# NTC_connector.net
KiCad netlist of a schematic drawn in Altium Designer
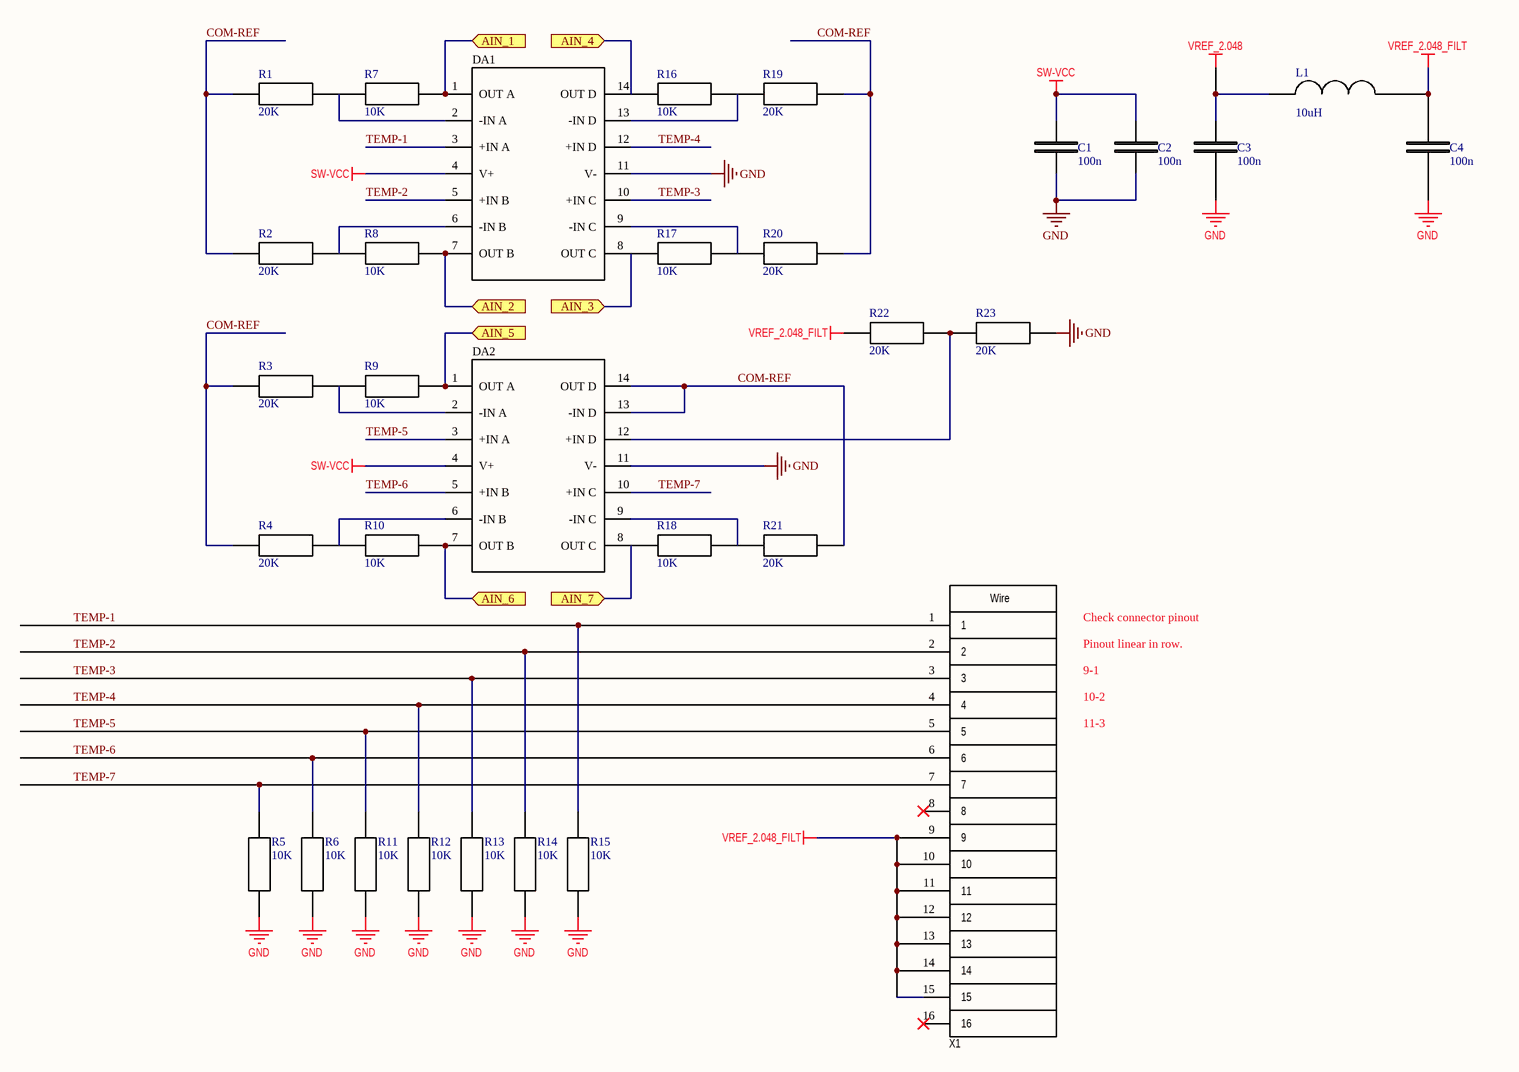
[diagram p0: NTC connector.SchDoc]

(export (version "E")
  (design (tool "Eeschema 10.0.6"))
  (components
    (comp (ref "C1")
      (value "100n")
      (footprint "CAP0402")
      (description "0402 SMD")
      (fields (field (name "PARTNUMBER") "CC0402ZRY5V7BB104") (field (name "MANUFACTURER") "Yageo"))
      (libsource (lib "capasitors") (part "100n SMD 0402"))
    )
    (comp (ref "C2")
      (value "100n")
      (footprint "CAP0402")
      (description "0402 SMD")
      (fields (field (name "PARTNUMBER") "CC0402ZRY5V7BB104") (field (name "MANUFACTURER") "Yageo"))
      (libsource (lib "capasitors") (part "100n SMD 0402"))
    )
    (comp (ref "C3")
      (value "100n")
      (footprint "CAP0402")
      (description "0402 SMD")
      (fields (field (name "PARTNUMBER") "CC0402ZRY5V7BB104") (field (name "MANUFACTURER") "Yageo"))
      (libsource (lib "capasitors") (part "100n SMD 0402"))
    )
    (comp (ref "C4")
      (value "100n")
      (footprint "CAP0402")
      (description "0402 SMD")
      (fields (field (name "PARTNUMBER") "CC0402ZRY5V7BB104") (field (name "MANUFACTURER") "Yageo"))
      (libsource (lib "capasitors") (part "100n SMD 0402"))
    )
    (comp (ref "DA1")
      (value "OPA4376")
      (footprint "TSSOP-14")
      (description "Opamp  2.2-5.5 V, Offset 5μV")
      (fields (field (name "PARTNUMBER") "OPA4376AIPW") (field (name "MANUFACTURER") "Texas Instruments"))
      (libsource (lib "opamp") (part "OPA4376"))
    )
    (comp (ref "DA2")
      (value "OPA4376")
      (footprint "TSSOP-14")
      (description "Opamp  2.2-5.5 V, Offset 5μV")
      (fields (field (name "PARTNUMBER") "OPA4376AIPW") (field (name "MANUFACTURER") "Texas Instruments"))
      (libsource (lib "opamp") (part "OPA4376"))
    )
    (comp (ref "L1")
      (value "10uH")
      (footprint "IND0805")
      (description "0805 SMD")
      (fields (field (name "PARTNUMBER") "LQM21FN100M80L") (field (name "MANUFACTURER") "Murata"))
      (libsource (lib "inductors") (part "IND 10uH SMD 0805"))
    )
    (comp (ref "R1")
      (value "20K")
      (footprint "RES0402")
      (description "1% 0402 SMD 0.063W")
      (fields (field (name "PARTNUMBER") "RC0402FR-0720KL") (field (name "MANUFACTURER") "Yageo"))
      (libsource (lib "resistors") (part "20K 1% SMD 0402"))
    )
    (comp (ref "R2")
      (value "20K")
      (footprint "RES0402")
      (description "1% 0402 SMD 0.063W")
      (fields (field (name "PARTNUMBER") "RC0402FR-0720KL") (field (name "MANUFACTURER") "Yageo"))
      (libsource (lib "resistors") (part "20K 1% SMD 0402"))
    )
    (comp (ref "R3")
      (value "20K")
      (footprint "RES0402")
      (description "1% 0402 SMD 0.063W")
      (fields (field (name "PARTNUMBER") "RC0402FR-0720KL") (field (name "MANUFACTURER") "Yageo"))
      (libsource (lib "resistors") (part "20K 1% SMD 0402"))
    )
    (comp (ref "R4")
      (value "20K")
      (footprint "RES0402")
      (description "1% 0402 SMD 0.063W")
      (fields (field (name "PARTNUMBER") "RC0402FR-0720KL") (field (name "MANUFACTURER") "Yageo"))
      (libsource (lib "resistors") (part "20K 1% SMD 0402"))
    )
    (comp (ref "R5")
      (value "10K")
      (footprint "RES0402")
      (description "1% 0402 SMD 0.063W")
      (fields (field (name "PARTNUMBER") "RC0402FR-0710KL") (field (name "MANUFACTURER") "Yageo"))
      (libsource (lib "resistors") (part "10K 1% SMD 0402"))
    )
    (comp (ref "R6")
      (value "10K")
      (footprint "RES0402")
      (description "1% 0402 SMD 0.063W")
      (fields (field (name "PARTNUMBER") "RC0402FR-0710KL") (field (name "MANUFACTURER") "Yageo"))
      (libsource (lib "resistors") (part "10K 1% SMD 0402"))
    )
    (comp (ref "R7")
      (value "10K")
      (footprint "RES0402")
      (description "1% 0402 SMD 0.063W")
      (fields (field (name "PARTNUMBER") "RC0402FR-0710KL") (field (name "MANUFACTURER") "Yageo"))
      (libsource (lib "resistors") (part "10K 1% SMD 0402"))
    )
    (comp (ref "R8")
      (value "10K")
      (footprint "RES0402")
      (description "1% 0402 SMD 0.063W")
      (fields (field (name "PARTNUMBER") "RC0402FR-0710KL") (field (name "MANUFACTURER") "Yageo"))
      (libsource (lib "resistors") (part "10K 1% SMD 0402"))
    )
    (comp (ref "R9")
      (value "10K")
      (footprint "RES0402")
      (description "1% 0402 SMD 0.063W")
      (fields (field (name "PARTNUMBER") "RC0402FR-0710KL") (field (name "MANUFACTURER") "Yageo"))
      (libsource (lib "resistors") (part "10K 1% SMD 0402"))
    )
    (comp (ref "R10")
      (value "10K")
      (footprint "RES0402")
      (description "1% 0402 SMD 0.063W")
      (fields (field (name "PARTNUMBER") "RC0402FR-0710KL") (field (name "MANUFACTURER") "Yageo"))
      (libsource (lib "resistors") (part "10K 1% SMD 0402"))
    )
    (comp (ref "R11")
      (value "10K")
      (footprint "RES0402")
      (description "1% 0402 SMD 0.063W")
      (fields (field (name "PARTNUMBER") "RC0402FR-0710KL") (field (name "MANUFACTURER") "Yageo"))
      (libsource (lib "resistors") (part "10K 1% SMD 0402"))
    )
    (comp (ref "R12")
      (value "10K")
      (footprint "RES0402")
      (description "1% 0402 SMD 0.063W")
      (fields (field (name "PARTNUMBER") "RC0402FR-0710KL") (field (name "MANUFACTURER") "Yageo"))
      (libsource (lib "resistors") (part "10K 1% SMD 0402"))
    )
    (comp (ref "R13")
      (value "10K")
      (footprint "RES0402")
      (description "1% 0402 SMD 0.063W")
      (fields (field (name "PARTNUMBER") "RC0402FR-0710KL") (field (name "MANUFACTURER") "Yageo"))
      (libsource (lib "resistors") (part "10K 1% SMD 0402"))
    )
    (comp (ref "R14")
      (value "10K")
      (footprint "RES0402")
      (description "1% 0402 SMD 0.063W")
      (fields (field (name "PARTNUMBER") "RC0402FR-0710KL") (field (name "MANUFACTURER") "Yageo"))
      (libsource (lib "resistors") (part "10K 1% SMD 0402"))
    )
    (comp (ref "R15")
      (value "10K")
      (footprint "RES0402")
      (description "1% 0402 SMD 0.063W")
      (fields (field (name "PARTNUMBER") "RC0402FR-0710KL") (field (name "MANUFACTURER") "Yageo"))
      (libsource (lib "resistors") (part "10K 1% SMD 0402"))
    )
    (comp (ref "R16")
      (value "10K")
      (footprint "RES0402")
      (description "1% 0402 SMD 0.063W")
      (fields (field (name "PARTNUMBER") "RC0402FR-0710KL") (field (name "MANUFACTURER") "Yageo"))
      (libsource (lib "resistors") (part "10K 1% SMD 0402"))
    )
    (comp (ref "R17")
      (value "10K")
      (footprint "RES0402")
      (description "1% 0402 SMD 0.063W")
      (fields (field (name "PARTNUMBER") "RC0402FR-0710KL") (field (name "MANUFACTURER") "Yageo"))
      (libsource (lib "resistors") (part "10K 1% SMD 0402"))
    )
    (comp (ref "R18")
      (value "10K")
      (footprint "RES0402")
      (description "1% 0402 SMD 0.063W")
      (fields (field (name "PARTNUMBER") "RC0402FR-0710KL") (field (name "MANUFACTURER") "Yageo"))
      (libsource (lib "resistors") (part "10K 1% SMD 0402"))
    )
    (comp (ref "R19")
      (value "20K")
      (footprint "RES0402")
      (description "1% 0402 SMD 0.063W")
      (fields (field (name "PARTNUMBER") "RC0402FR-0720KL") (field (name "MANUFACTURER") "Yageo"))
      (libsource (lib "resistors") (part "20K 1% SMD 0402"))
    )
    (comp (ref "R20")
      (value "20K")
      (footprint "RES0402")
      (description "1% 0402 SMD 0.063W")
      (fields (field (name "PARTNUMBER") "RC0402FR-0720KL") (field (name "MANUFACTURER") "Yageo"))
      (libsource (lib "resistors") (part "20K 1% SMD 0402"))
    )
    (comp (ref "R21")
      (value "20K")
      (footprint "RES0402")
      (description "1% 0402 SMD 0.063W")
      (fields (field (name "PARTNUMBER") "RC0402FR-0720KL") (field (name "MANUFACTURER") "Yageo"))
      (libsource (lib "resistors") (part "20K 1% SMD 0402"))
    )
    (comp (ref "R22")
      (value "20K")
      (footprint "RES0402")
      (description "1% 0402 SMD 0.063W")
      (fields (field (name "PARTNUMBER") "RC0402FR-0720KL") (field (name "MANUFACTURER") "Yageo"))
      (libsource (lib "resistors") (part "20K 1% SMD 0402"))
    )
    (comp (ref "R23")
      (value "20K")
      (footprint "RES0402")
      (description "1% 0402 SMD 0.063W")
      (fields (field (name "PARTNUMBER") "RC0402FR-0720KL") (field (name "MANUFACTURER") "Yageo"))
      (libsource (lib "resistors") (part "20K 1% SMD 0402"))
    )
    (comp (ref "X1")
      (value "Microfit3.0 16 pins R thru hole")
      (footprint "microfit30_16")
      (description "Step 3mm, dual row 16 pins, thru hole")
      (fields (field (name "PARTNUMBER") "43045-1601 molex") (field (name "MANUFACTURER") "Molex"))
      (libsource (lib "connectors") (part "Microfit3.0 16 pins R thru hole"))
    )
  )
  (nets
    (net (code "1") (name "/AIN_1") (class "Default")
      (node (ref "DA1") (pin "1") (pinfunction "OUT_A_1") (pintype "passive"))
      (node (ref "R7") (pin "1") (pinfunction "1_1") (pintype "passive"))
    )
    (net (code "2") (name "/AIN_2") (class "Default")
      (node (ref "DA1") (pin "7") (pinfunction "OUT_B_7") (pintype "passive"))
      (node (ref "R8") (pin "1") (pinfunction "1_1") (pintype "passive"))
    )
    (net (code "3") (name "/AIN_3") (class "Default")
      (node (ref "DA1") (pin "8") (pinfunction "OUT_C_8") (pintype "passive"))
      (node (ref "R17") (pin "2") (pinfunction "2_2") (pintype "passive"))
    )
    (net (code "4") (name "/AIN_4") (class "Default")
      (node (ref "DA1") (pin "14") (pinfunction "OUT_D_14") (pintype "passive"))
      (node (ref "R16") (pin "2") (pinfunction "2_2") (pintype "passive"))
    )
    (net (code "5") (name "/AIN_5") (class "Default")
      (node (ref "DA2") (pin "1") (pinfunction "OUT_A_1") (pintype "passive"))
      (node (ref "R9") (pin "1") (pinfunction "1_1") (pintype "passive"))
    )
    (net (code "6") (name "/AIN_6") (class "Default")
      (node (ref "DA2") (pin "7") (pinfunction "OUT_B_7") (pintype "passive"))
      (node (ref "R10") (pin "1") (pinfunction "1_1") (pintype "passive"))
    )
    (net (code "7") (name "/AIN_7") (class "Default")
      (node (ref "DA2") (pin "8") (pinfunction "OUT_C_8") (pintype "passive"))
      (node (ref "R18") (pin "2") (pinfunction "2_2") (pintype "passive"))
    )
    (net (code "8") (name "/COM-REF") (class "Default")
      (node (ref "DA2") (pin "13") (pinfunction "-IN_D_13") (pintype "passive"))
      (node (ref "DA2") (pin "14") (pinfunction "OUT_D_14") (pintype "passive"))
      (node (ref "R1") (pin "2") (pinfunction "2_2") (pintype "passive"))
      (node (ref "R19") (pin "1") (pinfunction "1_1") (pintype "passive"))
      (node (ref "R2") (pin "2") (pinfunction "2_2") (pintype "passive"))
      (node (ref "R20") (pin "1") (pinfunction "1_1") (pintype "passive"))
      (node (ref "R21") (pin "1") (pinfunction "1_1") (pintype "passive"))
      (node (ref "R3") (pin "2") (pinfunction "2_2") (pintype "passive"))
      (node (ref "R4") (pin "2") (pinfunction "2_2") (pintype "passive"))
    )
    (net (code "9") (name "/TEMP-1") (class "Default")
      (node (ref "DA1") (pin "3") (pinfunction "+IN_A_3") (pintype "passive"))
      (node (ref "R15") (pin "1") (pinfunction "1_1") (pintype "passive"))
      (node (ref "X1") (pin "1") (pinfunction "1_1") (pintype "passive"))
    )
    (net (code "10") (name "/TEMP-2") (class "Default")
      (node (ref "DA1") (pin "5") (pinfunction "+IN_B_5") (pintype "passive"))
      (node (ref "R14") (pin "1") (pinfunction "1_1") (pintype "passive"))
      (node (ref "X1") (pin "2") (pinfunction "2_2") (pintype "passive"))
    )
    (net (code "11") (name "/TEMP-3") (class "Default")
      (node (ref "DA1") (pin "10") (pinfunction "+IN_C_10") (pintype "passive"))
      (node (ref "R13") (pin "1") (pinfunction "1_1") (pintype "passive"))
      (node (ref "X1") (pin "3") (pinfunction "3_3") (pintype "passive"))
    )
    (net (code "12") (name "/TEMP-4") (class "Default")
      (node (ref "DA1") (pin "12") (pinfunction "+IN_D_12") (pintype "passive"))
      (node (ref "R12") (pin "1") (pinfunction "1_1") (pintype "passive"))
      (node (ref "X1") (pin "4") (pinfunction "4_4") (pintype "passive"))
    )
    (net (code "13") (name "/TEMP-5") (class "Default")
      (node (ref "DA2") (pin "3") (pinfunction "+IN_A_3") (pintype "passive"))
      (node (ref "R11") (pin "1") (pinfunction "1_1") (pintype "passive"))
      (node (ref "X1") (pin "5") (pinfunction "5_5") (pintype "passive"))
    )
    (net (code "14") (name "/TEMP-6") (class "Default")
      (node (ref "DA2") (pin "5") (pinfunction "+IN_B_5") (pintype "passive"))
      (node (ref "R6") (pin "1") (pinfunction "1_1") (pintype "passive"))
      (node (ref "X1") (pin "6") (pinfunction "6_6") (pintype "passive"))
    )
    (net (code "15") (name "/TEMP-7") (class "Default")
      (node (ref "DA2") (pin "10") (pinfunction "+IN_C_10") (pintype "passive"))
      (node (ref "R5") (pin "1") (pinfunction "1_1") (pintype "passive"))
      (node (ref "X1") (pin "7") (pinfunction "7_7") (pintype "passive"))
    )
    (net (code "16") (name "GND") (class "Default")
      (node (ref "C1") (pin "2") (pinfunction "2_2") (pintype "passive"))
      (node (ref "C2") (pin "2") (pinfunction "2_2") (pintype "passive"))
      (node (ref "C3") (pin "2") (pinfunction "2_2") (pintype "passive"))
      (node (ref "C4") (pin "2") (pinfunction "2_2") (pintype "passive"))
      (node (ref "DA1") (pin "11") (pinfunction "V-_11") (pintype "passive"))
      (node (ref "DA2") (pin "11") (pinfunction "V-_11") (pintype "passive"))
      (node (ref "R11") (pin "2") (pinfunction "2_2") (pintype "passive"))
      (node (ref "R12") (pin "2") (pinfunction "2_2") (pintype "passive"))
      (node (ref "R13") (pin "2") (pinfunction "2_2") (pintype "passive"))
      (node (ref "R14") (pin "2") (pinfunction "2_2") (pintype "passive"))
      (node (ref "R15") (pin "2") (pinfunction "2_2") (pintype "passive"))
      (node (ref "R23") (pin "2") (pinfunction "2_2") (pintype "passive"))
      (node (ref "R5") (pin "2") (pinfunction "2_2") (pintype "passive"))
      (node (ref "R6") (pin "2") (pinfunction "2_2") (pintype "passive"))
    )
    (net (code "17") (name "Net-(DA1--IN_A)") (class "Default")
      (node (ref "DA1") (pin "2") (pinfunction "-IN_A_2") (pintype "passive"))
      (node (ref "R1") (pin "1") (pinfunction "1_1") (pintype "passive"))
      (node (ref "R7") (pin "2") (pinfunction "2_2") (pintype "passive"))
    )
    (net (code "18") (name "Net-(DA1--IN_B)") (class "Default")
      (node (ref "DA1") (pin "6") (pinfunction "-IN_B_6") (pintype "passive"))
      (node (ref "R2") (pin "1") (pinfunction "1_1") (pintype "passive"))
      (node (ref "R8") (pin "2") (pinfunction "2_2") (pintype "passive"))
    )
    (net (code "19") (name "Net-(DA1--IN_C)") (class "Default")
      (node (ref "DA1") (pin "9") (pinfunction "-IN_C_9") (pintype "passive"))
      (node (ref "R17") (pin "1") (pinfunction "1_1") (pintype "passive"))
      (node (ref "R20") (pin "2") (pinfunction "2_2") (pintype "passive"))
    )
    (net (code "20") (name "Net-(DA1--IN_D)") (class "Default")
      (node (ref "DA1") (pin "13") (pinfunction "-IN_D_13") (pintype "passive"))
      (node (ref "R16") (pin "1") (pinfunction "1_1") (pintype "passive"))
      (node (ref "R19") (pin "2") (pinfunction "2_2") (pintype "passive"))
    )
    (net (code "21") (name "Net-(DA2-+IN_D)") (class "Default")
      (node (ref "DA2") (pin "12") (pinfunction "+IN_D_12") (pintype "passive"))
      (node (ref "R22") (pin "2") (pinfunction "2_2") (pintype "passive"))
      (node (ref "R23") (pin "1") (pinfunction "1_1") (pintype "passive"))
    )
    (net (code "22") (name "Net-(DA2--IN_A)") (class "Default")
      (node (ref "DA2") (pin "2") (pinfunction "-IN_A_2") (pintype "passive"))
      (node (ref "R3") (pin "1") (pinfunction "1_1") (pintype "passive"))
      (node (ref "R9") (pin "2") (pinfunction "2_2") (pintype "passive"))
    )
    (net (code "23") (name "Net-(DA2--IN_B)") (class "Default")
      (node (ref "DA2") (pin "6") (pinfunction "-IN_B_6") (pintype "passive"))
      (node (ref "R10") (pin "2") (pinfunction "2_2") (pintype "passive"))
      (node (ref "R4") (pin "1") (pinfunction "1_1") (pintype "passive"))
    )
    (net (code "24") (name "Net-(DA2--IN_C)") (class "Default")
      (node (ref "DA2") (pin "9") (pinfunction "-IN_C_9") (pintype "passive"))
      (node (ref "R18") (pin "1") (pinfunction "1_1") (pintype "passive"))
      (node (ref "R21") (pin "2") (pinfunction "2_2") (pintype "passive"))
    )
    (net (code "25") (name "SW-VCC") (class "Default")
      (node (ref "C1") (pin "1") (pinfunction "1_1") (pintype "passive"))
      (node (ref "C2") (pin "1") (pinfunction "1_1") (pintype "passive"))
      (node (ref "DA1") (pin "4") (pinfunction "V+_4") (pintype "passive"))
      (node (ref "DA2") (pin "4") (pinfunction "V+_4") (pintype "passive"))
    )
    (net (code "26") (name "VREF_2.048") (class "Default")
      (node (ref "C3") (pin "1") (pinfunction "1_1") (pintype "passive"))
      (node (ref "L1") (pin "1") (pinfunction "1_1") (pintype "passive"))
    )
    (net (code "27") (name "VREF_2.048_FILT") (class "Default")
      (node (ref "C4") (pin "1") (pinfunction "1_1") (pintype "passive"))
      (node (ref "L1") (pin "2") (pinfunction "2_2") (pintype "passive"))
      (node (ref "R22") (pin "1") (pinfunction "1_1") (pintype "passive"))
      (node (ref "X1") (pin "10") (pinfunction "10_10") (pintype "passive"))
      (node (ref "X1") (pin "11") (pinfunction "11_11") (pintype "passive"))
      (node (ref "X1") (pin "12") (pinfunction "12_12") (pintype "passive"))
      (node (ref "X1") (pin "13") (pinfunction "13_13") (pintype "passive"))
      (node (ref "X1") (pin "14") (pinfunction "14_14") (pintype "passive"))
      (node (ref "X1") (pin "15") (pinfunction "15_15") (pintype "passive"))
      (node (ref "X1") (pin "9") (pinfunction "9_9") (pintype "passive"))
    )
    (net (code "28") (name "unconnected-(X1-Pad8)") (class "Default")
      (node (ref "X1") (pin "8") (pinfunction "8_8") (pintype "passive+no_connect"))
    )
    (net (code "29") (name "unconnected-(X1-Pad16)") (class "Default")
      (node (ref "X1") (pin "16") (pinfunction "16_16") (pintype "passive+no_connect"))
    )
  )
)
